# PA_group.net
KiCad netlist of a schematic drawn in Altium Designer
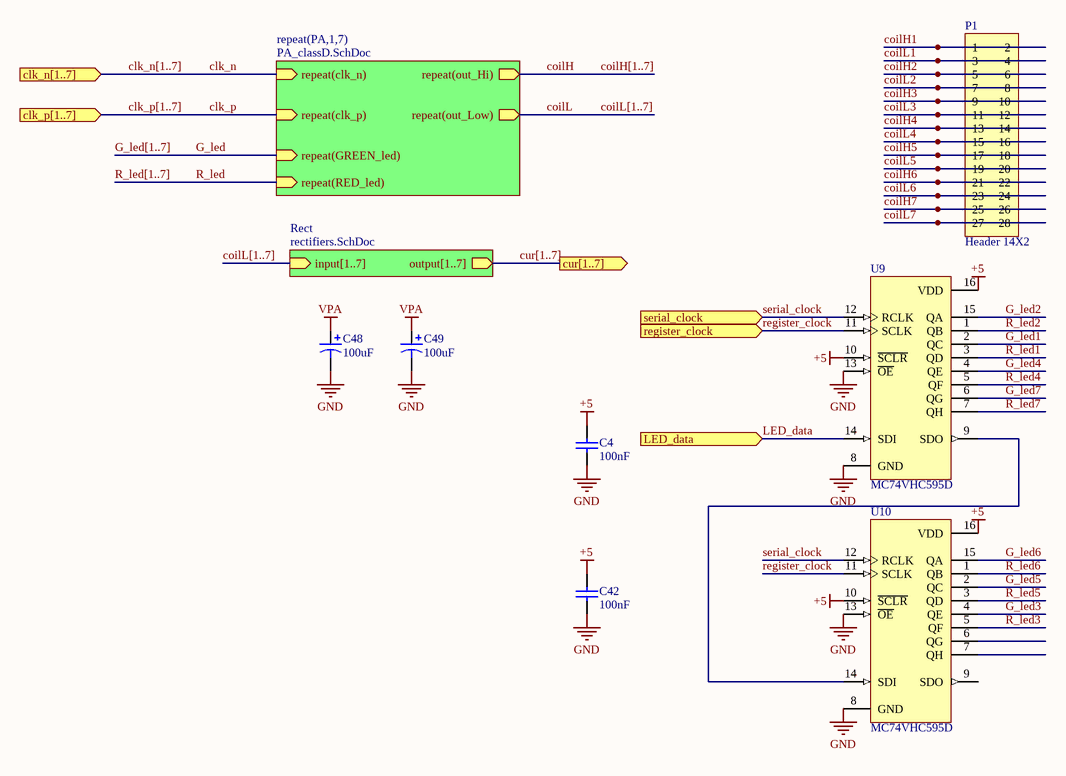
[diagram p0: PA_group.SchDoc]

(export (version "E")
  (design (tool "Eeschema 10.0.6"))
  (components
    (comp (ref "C4")
      (value "100nF")
      (footprint "SMD_CAP_0805")
      (description "CAP-100Nf")
      (libsource (lib "Altium library (www.AVRelec.com)") (part "Cap ceramic"))
    )
    (comp (ref "C42")
      (value "100nF")
      (footprint "SMD_CAP_0805")
      (description "CAP-100Nf")
      (libsource (lib "Altium library (www.AVRelec.com)") (part "Cap ceramic"))
    )
    (comp (ref "C48")
      (value "100uF")
      (footprint "Cap SMD electrolite-6.3mm")
      (description "Polarized Capacitor (Radial)")
      (fields (field (name "PUBLISHER") "Altium Limited"))
      (libsource (lib "Miscellaneous Devices") (part "Cap Pol1"))
    )
    (comp (ref "C49")
      (value "100uF")
      (footprint "Cap SMD electrolite-6.3mm")
      (description "Polarized Capacitor (Radial)")
      (fields (field (name "PUBLISHER") "Altium Limited"))
      (libsource (lib "Miscellaneous Devices") (part "Cap Pol1"))
    )
    (comp (ref "P1")
      (value "Header 14X2")
      (footprint "HDR2X14")
      (description "Header, 14-Pin, Dual row")
      (fields (field (name "PUBLISHER") "Altium Limited"))
      (libsource (lib "Miscellaneous Connectors") (part "Header 14X2"))
    )
    (comp (ref "U9")
      (value "MC74VHC595D")
      (footprint "751B-05_N")
      (description "8-Bit 3-State Shift Register with Output Storage Register")
      (fields (field (name "PUBLISHER") "Altium Limited"))
      (libsource (lib "ON Semi Logic Register") (part "MC74VHC595D"))
    )
    (comp (ref "U10")
      (value "MC74VHC595D")
      (footprint "751B-05_N")
      (description "8-Bit 3-State Shift Register with Output Storage Register")
      (fields (field (name "PUBLISHER") "Altium Limited"))
      (libsource (lib "ON Semi Logic Register") (part "MC74VHC595D"))
    )
  )
  (nets
    (net (code "22") (name "+5") (class "Default")
      (node (ref "C4") (pin "1") (pinfunction "1_1") (pintype "passive"))
      (node (ref "C42") (pin "1") (pinfunction "1_1") (pintype "passive"))
      (node (ref "U10") (pin "10") (pinfunction "~{SCLR}_10") (pintype "input"))
      (node (ref "U10") (pin "16") (pinfunction "VDD_16") (pintype "power_in"))
      (node (ref "U9") (pin "10") (pinfunction "~{SCLR}_10") (pintype "input"))
      (node (ref "U9") (pin "16") (pinfunction "VDD_16") (pintype "power_in"))
    )
    (net (code "24") (name "/G_led1") (class "Default")
      (node (ref "U9") (pin "2") (pinfunction "QC_2") (pintype "tri_state"))
    )
    (net (code "25") (name "/G_led2") (class "Default")
      (node (ref "U9") (pin "15") (pinfunction "QA_15") (pintype "tri_state"))
    )
    (net (code "26") (name "/G_led3") (class "Default")
      (node (ref "U10") (pin "4") (pinfunction "QE_4") (pintype "tri_state"))
    )
    (net (code "27") (name "/G_led4") (class "Default")
      (node (ref "U9") (pin "4") (pinfunction "QE_4") (pintype "tri_state"))
    )
    (net (code "28") (name "/G_led5") (class "Default")
      (node (ref "U10") (pin "2") (pinfunction "QC_2") (pintype "tri_state"))
    )
    (net (code "29") (name "/G_led6") (class "Default")
      (node (ref "U10") (pin "15") (pinfunction "QA_15") (pintype "tri_state"))
    )
    (net (code "30") (name "/G_led7") (class "Default")
      (node (ref "U9") (pin "6") (pinfunction "QG_6") (pintype "tri_state"))
    )
    (net (code "32") (name "/LED_data") (class "Default")
      (node (ref "U9") (pin "14") (pinfunction "SDI_14") (pintype "input"))
    )
    (net (code "34") (name "/R_led1") (class "Default")
      (node (ref "U9") (pin "3") (pinfunction "QD_3") (pintype "tri_state"))
    )
    (net (code "35") (name "/R_led2") (class "Default")
      (node (ref "U9") (pin "1") (pinfunction "QB_1") (pintype "tri_state"))
    )
    (net (code "36") (name "/R_led3") (class "Default")
      (node (ref "U10") (pin "5") (pinfunction "QF_5") (pintype "tri_state"))
    )
    (net (code "37") (name "/R_led4") (class "Default")
      (node (ref "U9") (pin "5") (pinfunction "QF_5") (pintype "tri_state"))
    )
    (net (code "38") (name "/R_led5") (class "Default")
      (node (ref "U10") (pin "3") (pinfunction "QD_3") (pintype "tri_state"))
    )
    (net (code "39") (name "/R_led6") (class "Default")
      (node (ref "U10") (pin "1") (pinfunction "QB_1") (pintype "tri_state"))
    )
    (net (code "40") (name "/R_led7") (class "Default")
      (node (ref "U9") (pin "7") (pinfunction "QH_7") (pintype "tri_state"))
    )
    (net (code "47") (name "/coilH1") (class "Default")
      (node (ref "P1") (pin "1") (pinfunction "1_1") (pintype "passive"))
      (node (ref "P1") (pin "2") (pinfunction "2_2") (pintype "passive"))
    )
    (net (code "48") (name "/coilH2") (class "Default")
      (node (ref "P1") (pin "5") (pinfunction "5_5") (pintype "passive"))
      (node (ref "P1") (pin "6") (pinfunction "6_6") (pintype "passive"))
    )
    (net (code "49") (name "/coilH3") (class "Default")
      (node (ref "P1") (pin "10") (pinfunction "10_10") (pintype "passive"))
      (node (ref "P1") (pin "9") (pinfunction "9_9") (pintype "passive"))
    )
    (net (code "50") (name "/coilH4") (class "Default")
      (node (ref "P1") (pin "13") (pinfunction "13_13") (pintype "passive"))
      (node (ref "P1") (pin "14") (pinfunction "14_14") (pintype "passive"))
    )
    (net (code "51") (name "/coilH5") (class "Default")
      (node (ref "P1") (pin "17") (pinfunction "17_17") (pintype "passive"))
      (node (ref "P1") (pin "18") (pinfunction "18_18") (pintype "passive"))
    )
    (net (code "52") (name "/coilH6") (class "Default")
      (node (ref "P1") (pin "21") (pinfunction "21_21") (pintype "passive"))
      (node (ref "P1") (pin "22") (pinfunction "22_22") (pintype "passive"))
    )
    (net (code "53") (name "/coilH7") (class "Default")
      (node (ref "P1") (pin "25") (pinfunction "25_25") (pintype "passive"))
      (node (ref "P1") (pin "26") (pinfunction "26_26") (pintype "passive"))
    )
    (net (code "56") (name "/coilL1") (class "Default")
      (node (ref "P1") (pin "3") (pinfunction "3_3") (pintype "passive"))
      (node (ref "P1") (pin "4") (pinfunction "4_4") (pintype "passive"))
    )
    (net (code "57") (name "/coilL2") (class "Default")
      (node (ref "P1") (pin "7") (pinfunction "7_7") (pintype "passive"))
      (node (ref "P1") (pin "8") (pinfunction "8_8") (pintype "passive"))
    )
    (net (code "58") (name "/coilL3") (class "Default")
      (node (ref "P1") (pin "11") (pinfunction "11_11") (pintype "passive"))
      (node (ref "P1") (pin "12") (pinfunction "12_12") (pintype "passive"))
    )
    (net (code "59") (name "/coilL4") (class "Default")
      (node (ref "P1") (pin "15") (pinfunction "15_15") (pintype "passive"))
      (node (ref "P1") (pin "16") (pinfunction "16_16") (pintype "passive"))
    )
    (net (code "60") (name "/coilL5") (class "Default")
      (node (ref "P1") (pin "19") (pinfunction "19_19") (pintype "passive"))
      (node (ref "P1") (pin "20") (pinfunction "20_20") (pintype "passive"))
    )
    (net (code "61") (name "/coilL6") (class "Default")
      (node (ref "P1") (pin "23") (pinfunction "23_23") (pintype "passive"))
      (node (ref "P1") (pin "24") (pinfunction "24_24") (pintype "passive"))
    )
    (net (code "62") (name "/coilL7") (class "Default")
      (node (ref "P1") (pin "27") (pinfunction "27_27") (pintype "passive"))
      (node (ref "P1") (pin "28") (pinfunction "28_28") (pintype "passive"))
    )
    (net (code "65") (name "/register_clock") (class "Default")
      (node (ref "U10") (pin "11") (pinfunction "SCLK_11") (pintype "input"))
      (node (ref "U9") (pin "11") (pinfunction "SCLK_11") (pintype "input"))
    )
    (net (code "66") (name "/serial_clock") (class "Default")
      (node (ref "U10") (pin "12") (pinfunction "RCLK_12") (pintype "input"))
      (node (ref "U9") (pin "12") (pinfunction "RCLK_12") (pintype "input"))
    )
    (net (code "67") (name "GND") (class "Default")
      (node (ref "C4") (pin "2") (pinfunction "2_2") (pintype "passive"))
      (node (ref "C42") (pin "2") (pinfunction "2_2") (pintype "passive"))
      (node (ref "C48") (pin "2") (pinfunction "2_2") (pintype "passive"))
      (node (ref "C49") (pin "2") (pinfunction "2_2") (pintype "passive"))
      (node (ref "U10") (pin "13") (pinfunction "~{OE}_13") (pintype "input"))
      (node (ref "U10") (pin "8") (pinfunction "GND_8") (pintype "power_in"))
      (node (ref "U9") (pin "13") (pinfunction "~{OE}_13") (pintype "input"))
      (node (ref "U9") (pin "8") (pinfunction "GND_8") (pintype "power_in"))
    )
    (net (code "68") (name "Net-(U10-SDI)") (class "Default")
      (node (ref "U10") (pin "14") (pinfunction "SDI_14") (pintype "input"))
      (node (ref "U9") (pin "9") (pinfunction "SDO_9") (pintype "output"))
    )
    (net (code "69") (name "VPA") (class "Default")
      (node (ref "C48") (pin "1") (pinfunction "1_1") (pintype "passive"))
      (node (ref "C49") (pin "1") (pinfunction "1_1") (pintype "passive"))
    )
    (net (code "70") (name "unconnected-(U10-QG-Pad6)") (class "Default")
      (node (ref "U10") (pin "6") (pinfunction "QG_6") (pintype "tri_state"))
    )
    (net (code "71") (name "unconnected-(U10-QH-Pad7)") (class "Default")
      (node (ref "U10") (pin "7") (pinfunction "QH_7") (pintype "tri_state"))
    )
    (net (code "72") (name "unconnected-(U10-SDO-Pad9)") (class "Default")
      (node (ref "U10") (pin "9") (pinfunction "SDO_9") (pintype "output"))
    )
  )
)
